# INF_Pro_Interface.net
KiCad netlist of a schematic drawn in Altium Designer
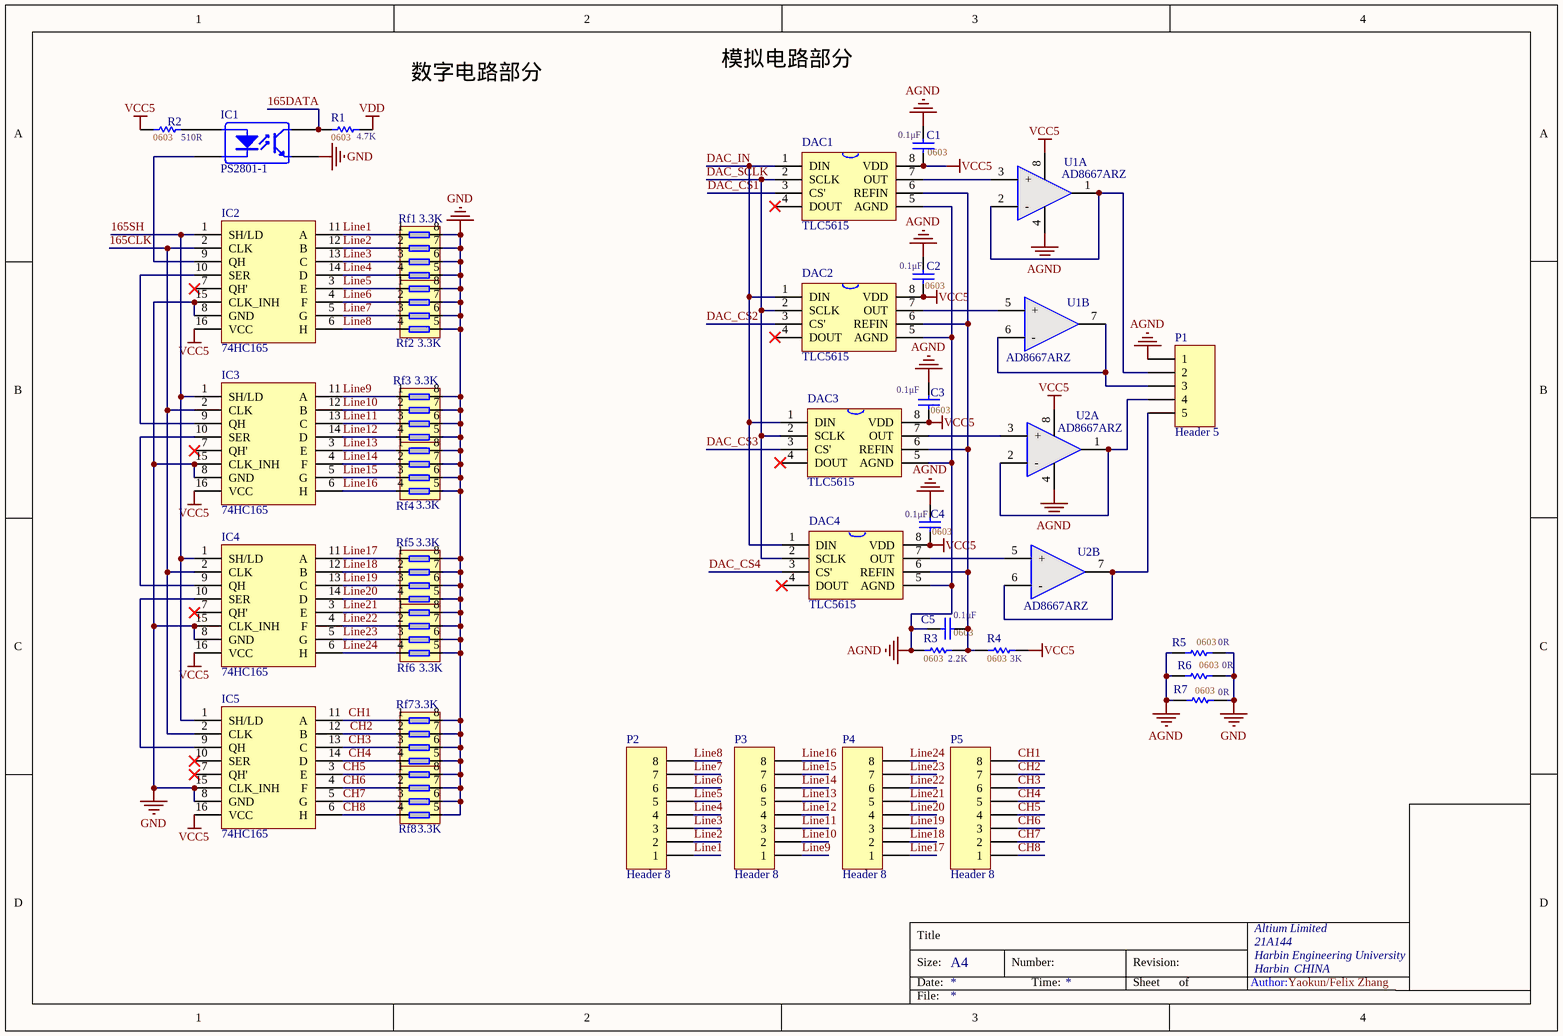
[diagram p0: INF_Pro_Interface.SchDoc]

(export (version "E")
  (design (tool "Eeschema 10.0.6"))
  (components
    (comp (ref "C1")
      (value "0.1μF")
      (footprint "CAP_0603_16*08")
      (description "Capacitor")
      (fields
        (field (name "PACKAGEREFERENCE") "0603")
        (field (name "Comment") "0603")
        (field (name "PUBLISHER") "Altium Limited")
      )
      (libsource (lib "Belong_to_Kongkong") (part "Cap"))
    )
    (comp (ref "C2")
      (value "0.1μF")
      (footprint "CAP_0603_16*08")
      (description "Capacitor")
      (fields
        (field (name "PACKAGEREFERENCE") "0603")
        (field (name "Comment") "0603")
        (field (name "PUBLISHER") "Altium Limited")
      )
      (libsource (lib "Belong_to_Kongkong") (part "Cap"))
    )
    (comp (ref "C3")
      (value "0.1μF")
      (footprint "CAP_0603_16*08")
      (description "Capacitor")
      (fields
        (field (name "PACKAGEREFERENCE") "0603")
        (field (name "Comment") "0603")
        (field (name "PUBLISHER") "Altium Limited")
      )
      (libsource (lib "Belong_to_Kongkong") (part "Cap"))
    )
    (comp (ref "C4")
      (value "0.1μF")
      (footprint "CAP_0603_16*08")
      (description "Capacitor")
      (fields
        (field (name "PACKAGEREFERENCE") "0603")
        (field (name "Comment") "0603")
        (field (name "PUBLISHER") "Altium Limited")
      )
      (libsource (lib "Belong_to_Kongkong") (part "Cap"))
    )
    (comp (ref "C5")
      (value "0.1μF")
      (footprint "CAP_0603_16*08")
      (description "Capacitor")
      (fields
        (field (name "PACKAGEREFERENCE") "0603")
        (field (name "Comment") "0603")
        (field (name "PUBLISHER") "Altium Limited")
      )
      (libsource (lib "Belong_to_Kongkong") (part "Cap"))
    )
    (comp (ref "DAC1")
      (value "TLC5615")
      (footprint "DIP-8")
      (libsource (lib "Belong_to_Kongkong") (part "TLC5616_DAC"))
    )
    (comp (ref "DAC2")
      (value "TLC5615")
      (footprint "DIP-8")
      (libsource (lib "Belong_to_Kongkong") (part "TLC5616_DAC"))
    )
    (comp (ref "DAC3")
      (value "TLC5615")
      (footprint "DIP-8")
      (libsource (lib "Belong_to_Kongkong") (part "TLC5616_DAC"))
    )
    (comp (ref "DAC4")
      (value "TLC5615")
      (footprint "DIP-8")
      (libsource (lib "Belong_to_Kongkong") (part "TLC5616_DAC"))
    )
    (comp (ref "IC1")
      (value "PS2801-1")
      (footprint "DIP-4")
      (libsource (lib "Belong_to_Kongkong") (part "PS2801-1"))
    )
    (comp (ref "IC2")
      (value "74HC165")
      (footprint "DIP-16")
      (libsource (lib "Belong_to_Kongkong") (part "74HC165"))
    )
    (comp (ref "IC3")
      (value "74HC165")
      (footprint "DIP-16")
      (libsource (lib "Belong_to_Kongkong") (part "74HC165"))
    )
    (comp (ref "IC4")
      (value "74HC165")
      (footprint "DIP-16")
      (libsource (lib "Belong_to_Kongkong") (part "74HC165"))
    )
    (comp (ref "IC5")
      (value "74HC165")
      (footprint "DIP-16")
      (libsource (lib "Belong_to_Kongkong") (part "74HC165"))
    )
    (comp (ref "P1")
      (value "Header 5")
      (footprint "P5_OUT")
      (description "Header, 5-Pin")
      (fields (field (name "PUBLISHER") "Altium Limited"))
      (libsource (lib "Belong_to_Kongkong") (part "Header 5"))
    )
    (comp (ref "P2")
      (value "Header 8")
      (footprint "P8_OUT")
      (description "Header, 8-Pin")
      (fields (field (name "PUBLISHER") "Altium Limited"))
      (libsource (lib "Belong_to_Kongkong") (part "Header 8"))
    )
    (comp (ref "P3")
      (value "Header 8")
      (footprint "P8_OUT")
      (description "Header, 8-Pin")
      (fields (field (name "PUBLISHER") "Altium Limited"))
      (libsource (lib "Belong_to_Kongkong") (part "Header 8"))
    )
    (comp (ref "P4")
      (value "Header 8")
      (footprint "P8_OUT")
      (description "Header, 8-Pin")
      (fields (field (name "PUBLISHER") "Altium Limited"))
      (libsource (lib "Belong_to_Kongkong") (part "Header 8"))
    )
    (comp (ref "P5")
      (value "Header 8")
      (footprint "P8_OUT")
      (description "Header, 8-Pin")
      (fields (field (name "PUBLISHER") "Altium Limited"))
      (libsource (lib "Belong_to_Kongkong") (part "Header 8"))
    )
    (comp (ref "R1")
      (value "4.7K")
      (footprint "RES_0805_20*12")
      (description "Resistor")
      (fields
        (field (name "PACKAGEREFERENCE") "0603")
        (field (name "Comment") "SMD")
        (field (name "PUBLISHER") "Altium Limited")
      )
      (libsource (lib "Belong_to_Kongkong") (part "RES_SMD"))
    )
    (comp (ref "R2")
      (value "510R")
      (footprint "RES_0805_20*12")
      (description "Resistor")
      (fields
        (field (name "PACKAGEREFERENCE") "0603")
        (field (name "Comment") "SMD")
        (field (name "PUBLISHER") "Altium Limited")
      )
      (libsource (lib "Belong_to_Kongkong") (part "RES_SMD"))
    )
    (comp (ref "R3")
      (value "2.2K")
      (footprint "RES_0805_20*12")
      (description "Resistor")
      (fields
        (field (name "PACKAGEREFERENCE") "0603")
        (field (name "Comment") "SMD")
        (field (name "PUBLISHER") "Altium Limited")
      )
      (libsource (lib "Belong_to_Kongkong") (part "RES_SMD"))
    )
    (comp (ref "R4")
      (value "3K")
      (footprint "RES_0805_20*12")
      (description "Resistor")
      (fields
        (field (name "PACKAGEREFERENCE") "0603")
        (field (name "Comment") "SMD")
        (field (name "PUBLISHER") "Altium Limited")
      )
      (libsource (lib "Belong_to_Kongkong") (part "RES_SMD"))
    )
    (comp (ref "R5")
      (value "0R")
      (footprint "RES_0805_20*12")
      (description "Resistor")
      (fields
        (field (name "PACKAGEREFERENCE") "0603")
        (field (name "Comment") "SMD")
        (field (name "PUBLISHER") "Altium Limited")
      )
      (libsource (lib "Belong_to_Kongkong") (part "RES_SMD"))
    )
    (comp (ref "R6")
      (value "0R")
      (footprint "RES_0805_20*12")
      (description "Resistor")
      (fields
        (field (name "PACKAGEREFERENCE") "0603")
        (field (name "Comment") "SMD")
        (field (name "PUBLISHER") "Altium Limited")
      )
      (libsource (lib "Belong_to_Kongkong") (part "RES_SMD"))
    )
    (comp (ref "R7")
      (value "0R")
      (footprint "RES_0805_20*12")
      (description "Resistor")
      (fields
        (field (name "PACKAGEREFERENCE") "0603")
        (field (name "Comment") "SMD")
        (field (name "PUBLISHER") "Altium Limited")
      )
      (libsource (lib "Belong_to_Kongkong") (part "RES_SMD"))
    )
    (comp (ref "Rf1")
      (value "3.3K")
      (footprint "RES_FOUR_0603")
      (libsource (lib "Belong_to_Kongkong") (part "RES_4P"))
    )
    (comp (ref "Rf2")
      (value "3.3K")
      (footprint "RES_FOUR_0603")
      (libsource (lib "Belong_to_Kongkong") (part "RES_4P"))
    )
    (comp (ref "Rf3")
      (value "3.3K")
      (footprint "RES_FOUR_0603")
      (libsource (lib "Belong_to_Kongkong") (part "RES_4P"))
    )
    (comp (ref "Rf4")
      (value "3.3K")
      (footprint "RES_FOUR_0603")
      (libsource (lib "Belong_to_Kongkong") (part "RES_4P"))
    )
    (comp (ref "Rf5")
      (value "3.3K")
      (footprint "RES_FOUR_0603")
      (libsource (lib "Belong_to_Kongkong") (part "RES_4P"))
    )
    (comp (ref "Rf6")
      (value "3.3K")
      (footprint "RES_FOUR_0603")
      (libsource (lib "Belong_to_Kongkong") (part "RES_4P"))
    )
    (comp (ref "Rf7")
      (value "3.3K")
      (footprint "RES_FOUR_0603")
      (libsource (lib "Belong_to_Kongkong") (part "RES_4P"))
    )
    (comp (ref "Rf8")
      (value "3.3K")
      (footprint "RES_FOUR_0603")
      (libsource (lib "Belong_to_Kongkong") (part "RES_4P"))
    )
    (comp (ref "U1")
      (value "AD8667ARZ")
      (footprint "DIP-8")
      (description "双运放")
      (libsource (lib "Belong_to_Kongkong") (part "AD8667"))
    )
    (comp (ref "U2")
      (value "AD8667ARZ")
      (footprint "DIP-8")
      (description "双运放")
      (libsource (lib "Belong_to_Kongkong") (part "AD8667"))
    )
  )
  (nets
    (net (code "1") (name "/165CLK") (class "Default")
      (node (ref "IC2") (pin "2") (pinfunction "CLK_2") (pintype "passive"))
      (node (ref "IC3") (pin "2") (pinfunction "CLK_2") (pintype "passive"))
      (node (ref "IC4") (pin "2") (pinfunction "CLK_2") (pintype "passive"))
      (node (ref "IC5") (pin "2") (pinfunction "CLK_2") (pintype "passive"))
    )
    (net (code "2") (name "/165DATA") (class "Default")
      (node (ref "IC1") (pin "4") (pinfunction "4_4") (pintype "passive"))
      (node (ref "R1") (pin "1") (pinfunction "1_1") (pintype "passive"))
    )
    (net (code "3") (name "/165SH") (class "Default")
      (node (ref "IC2") (pin "1") (pinfunction "SH/LD_1") (pintype "passive"))
      (node (ref "IC3") (pin "1") (pinfunction "SH/LD_1") (pintype "passive"))
      (node (ref "IC4") (pin "1") (pinfunction "SH/LD_1") (pintype "passive"))
      (node (ref "IC5") (pin "1") (pinfunction "SH/LD_1") (pintype "passive"))
    )
    (net (code "4") (name "/CH1") (class "Default")
      (node (ref "IC5") (pin "11") (pinfunction "A_11") (pintype "passive"))
      (node (ref "P5") (pin "8") (pinfunction "8_8") (pintype "passive"))
      (node (ref "Rf7") (pin "1") (pinfunction "1_1") (pintype "passive"))
    )
    (net (code "5") (name "/CH2") (class "Default")
      (node (ref "IC5") (pin "12") (pinfunction "B_12") (pintype "passive"))
      (node (ref "P5") (pin "7") (pinfunction "7_7") (pintype "passive"))
      (node (ref "Rf7") (pin "2") (pinfunction "2_2") (pintype "passive"))
    )
    (net (code "6") (name "/CH3") (class "Default")
      (node (ref "IC5") (pin "13") (pinfunction "C_13") (pintype "passive"))
      (node (ref "P5") (pin "6") (pinfunction "6_6") (pintype "passive"))
      (node (ref "Rf7") (pin "3") (pinfunction "3_3") (pintype "passive"))
    )
    (net (code "7") (name "/CH4") (class "Default")
      (node (ref "IC5") (pin "14") (pinfunction "D_14") (pintype "passive"))
      (node (ref "P5") (pin "5") (pinfunction "5_5") (pintype "passive"))
      (node (ref "Rf7") (pin "4") (pinfunction "4_4") (pintype "passive"))
    )
    (net (code "8") (name "/CH5") (class "Default")
      (node (ref "IC5") (pin "3") (pinfunction "E_3") (pintype "passive"))
      (node (ref "P5") (pin "4") (pinfunction "4_4") (pintype "passive"))
      (node (ref "Rf8") (pin "1") (pinfunction "1_1") (pintype "passive"))
    )
    (net (code "9") (name "/CH6") (class "Default")
      (node (ref "IC5") (pin "4") (pinfunction "F_4") (pintype "passive"))
      (node (ref "P5") (pin "3") (pinfunction "3_3") (pintype "passive"))
      (node (ref "Rf8") (pin "2") (pinfunction "2_2") (pintype "passive"))
    )
    (net (code "10") (name "/CH7") (class "Default")
      (node (ref "IC5") (pin "5") (pinfunction "G_5") (pintype "passive"))
      (node (ref "P5") (pin "2") (pinfunction "2_2") (pintype "passive"))
      (node (ref "Rf8") (pin "3") (pinfunction "3_3") (pintype "passive"))
    )
    (net (code "11") (name "/CH8") (class "Default")
      (node (ref "IC5") (pin "6") (pinfunction "H_6") (pintype "passive"))
      (node (ref "P5") (pin "1") (pinfunction "1_1") (pintype "passive"))
      (node (ref "Rf8") (pin "4") (pinfunction "4_4") (pintype "passive"))
    )
    (net (code "12") (name "/DAC_CS1") (class "Default")
      (node (ref "DAC1") (pin "3") (pinfunction "CS'_3") (pintype "passive"))
    )
    (net (code "13") (name "/DAC_CS2") (class "Default")
      (node (ref "DAC2") (pin "3") (pinfunction "CS'_3") (pintype "passive"))
    )
    (net (code "14") (name "/DAC_CS3") (class "Default")
      (node (ref "DAC3") (pin "3") (pinfunction "CS'_3") (pintype "passive"))
    )
    (net (code "15") (name "/DAC_CS4") (class "Default")
      (node (ref "DAC4") (pin "3") (pinfunction "CS'_3") (pintype "passive"))
    )
    (net (code "16") (name "/DAC_IN") (class "Default")
      (node (ref "DAC1") (pin "1") (pinfunction "DIN_1") (pintype "passive"))
      (node (ref "DAC2") (pin "1") (pinfunction "DIN_1") (pintype "passive"))
      (node (ref "DAC3") (pin "1") (pinfunction "DIN_1") (pintype "passive"))
      (node (ref "DAC4") (pin "1") (pinfunction "DIN_1") (pintype "passive"))
    )
    (net (code "17") (name "/DAC_SCLK") (class "Default")
      (node (ref "DAC1") (pin "2") (pinfunction "SCLK_2") (pintype "passive"))
      (node (ref "DAC2") (pin "2") (pinfunction "SCLK_2") (pintype "passive"))
      (node (ref "DAC3") (pin "2") (pinfunction "SCLK_2") (pintype "passive"))
      (node (ref "DAC4") (pin "2") (pinfunction "SCLK_2") (pintype "passive"))
    )
    (net (code "18") (name "/Line1") (class "Default")
      (node (ref "IC2") (pin "11") (pinfunction "A_11") (pintype "passive"))
      (node (ref "P2") (pin "1") (pinfunction "1_1") (pintype "passive"))
      (node (ref "Rf1") (pin "1") (pinfunction "1_1") (pintype "passive"))
    )
    (net (code "19") (name "/Line2") (class "Default")
      (node (ref "IC2") (pin "12") (pinfunction "B_12") (pintype "passive"))
      (node (ref "P2") (pin "2") (pinfunction "2_2") (pintype "passive"))
      (node (ref "Rf1") (pin "2") (pinfunction "2_2") (pintype "passive"))
    )
    (net (code "20") (name "/Line3") (class "Default")
      (node (ref "IC2") (pin "13") (pinfunction "C_13") (pintype "passive"))
      (node (ref "P2") (pin "3") (pinfunction "3_3") (pintype "passive"))
      (node (ref "Rf1") (pin "3") (pinfunction "3_3") (pintype "passive"))
    )
    (net (code "21") (name "/Line4") (class "Default")
      (node (ref "IC2") (pin "14") (pinfunction "D_14") (pintype "passive"))
      (node (ref "P2") (pin "4") (pinfunction "4_4") (pintype "passive"))
      (node (ref "Rf1") (pin "4") (pinfunction "4_4") (pintype "passive"))
    )
    (net (code "22") (name "/Line5") (class "Default")
      (node (ref "IC2") (pin "3") (pinfunction "E_3") (pintype "passive"))
      (node (ref "P2") (pin "5") (pinfunction "5_5") (pintype "passive"))
      (node (ref "Rf2") (pin "1") (pinfunction "1_1") (pintype "passive"))
    )
    (net (code "23") (name "/Line6") (class "Default")
      (node (ref "IC2") (pin "4") (pinfunction "F_4") (pintype "passive"))
      (node (ref "P2") (pin "6") (pinfunction "6_6") (pintype "passive"))
      (node (ref "Rf2") (pin "2") (pinfunction "2_2") (pintype "passive"))
    )
    (net (code "24") (name "/Line7") (class "Default")
      (node (ref "IC2") (pin "5") (pinfunction "G_5") (pintype "passive"))
      (node (ref "P2") (pin "7") (pinfunction "7_7") (pintype "passive"))
      (node (ref "Rf2") (pin "3") (pinfunction "3_3") (pintype "passive"))
    )
    (net (code "25") (name "/Line8") (class "Default")
      (node (ref "IC2") (pin "6") (pinfunction "H_6") (pintype "passive"))
      (node (ref "P2") (pin "8") (pinfunction "8_8") (pintype "passive"))
      (node (ref "Rf2") (pin "4") (pinfunction "4_4") (pintype "passive"))
    )
    (net (code "26") (name "/Line9") (class "Default")
      (node (ref "IC3") (pin "11") (pinfunction "A_11") (pintype "passive"))
      (node (ref "P3") (pin "1") (pinfunction "1_1") (pintype "passive"))
      (node (ref "Rf3") (pin "1") (pinfunction "1_1") (pintype "passive"))
    )
    (net (code "27") (name "/Line10") (class "Default")
      (node (ref "IC3") (pin "12") (pinfunction "B_12") (pintype "passive"))
      (node (ref "P3") (pin "2") (pinfunction "2_2") (pintype "passive"))
      (node (ref "Rf3") (pin "2") (pinfunction "2_2") (pintype "passive"))
    )
    (net (code "28") (name "/Line11") (class "Default")
      (node (ref "IC3") (pin "13") (pinfunction "C_13") (pintype "passive"))
      (node (ref "P3") (pin "3") (pinfunction "3_3") (pintype "passive"))
      (node (ref "Rf3") (pin "3") (pinfunction "3_3") (pintype "passive"))
    )
    (net (code "29") (name "/Line12") (class "Default")
      (node (ref "IC3") (pin "14") (pinfunction "D_14") (pintype "passive"))
      (node (ref "P3") (pin "4") (pinfunction "4_4") (pintype "passive"))
      (node (ref "Rf3") (pin "4") (pinfunction "4_4") (pintype "passive"))
    )
    (net (code "30") (name "/Line13") (class "Default")
      (node (ref "IC3") (pin "3") (pinfunction "E_3") (pintype "passive"))
      (node (ref "P3") (pin "5") (pinfunction "5_5") (pintype "passive"))
      (node (ref "Rf4") (pin "1") (pinfunction "1_1") (pintype "passive"))
    )
    (net (code "31") (name "/Line14") (class "Default")
      (node (ref "IC3") (pin "4") (pinfunction "F_4") (pintype "passive"))
      (node (ref "P3") (pin "6") (pinfunction "6_6") (pintype "passive"))
      (node (ref "Rf4") (pin "2") (pinfunction "2_2") (pintype "passive"))
    )
    (net (code "32") (name "/Line15") (class "Default")
      (node (ref "IC3") (pin "5") (pinfunction "G_5") (pintype "passive"))
      (node (ref "P3") (pin "7") (pinfunction "7_7") (pintype "passive"))
      (node (ref "Rf4") (pin "3") (pinfunction "3_3") (pintype "passive"))
    )
    (net (code "33") (name "/Line16") (class "Default")
      (node (ref "IC3") (pin "6") (pinfunction "H_6") (pintype "passive"))
      (node (ref "P3") (pin "8") (pinfunction "8_8") (pintype "passive"))
      (node (ref "Rf4") (pin "4") (pinfunction "4_4") (pintype "passive"))
    )
    (net (code "34") (name "/Line17") (class "Default")
      (node (ref "IC4") (pin "11") (pinfunction "A_11") (pintype "passive"))
      (node (ref "P4") (pin "1") (pinfunction "1_1") (pintype "passive"))
      (node (ref "Rf5") (pin "1") (pinfunction "1_1") (pintype "passive"))
    )
    (net (code "35") (name "/Line18") (class "Default")
      (node (ref "IC4") (pin "12") (pinfunction "B_12") (pintype "passive"))
      (node (ref "P4") (pin "2") (pinfunction "2_2") (pintype "passive"))
      (node (ref "Rf5") (pin "2") (pinfunction "2_2") (pintype "passive"))
    )
    (net (code "36") (name "/Line19") (class "Default")
      (node (ref "IC4") (pin "13") (pinfunction "C_13") (pintype "passive"))
      (node (ref "P4") (pin "3") (pinfunction "3_3") (pintype "passive"))
      (node (ref "Rf5") (pin "3") (pinfunction "3_3") (pintype "passive"))
    )
    (net (code "37") (name "/Line20") (class "Default")
      (node (ref "IC4") (pin "14") (pinfunction "D_14") (pintype "passive"))
      (node (ref "P4") (pin "4") (pinfunction "4_4") (pintype "passive"))
      (node (ref "Rf5") (pin "4") (pinfunction "4_4") (pintype "passive"))
    )
    (net (code "38") (name "/Line21") (class "Default")
      (node (ref "IC4") (pin "3") (pinfunction "E_3") (pintype "passive"))
      (node (ref "P4") (pin "5") (pinfunction "5_5") (pintype "passive"))
      (node (ref "Rf6") (pin "1") (pinfunction "1_1") (pintype "passive"))
    )
    (net (code "39") (name "/Line22") (class "Default")
      (node (ref "IC4") (pin "4") (pinfunction "F_4") (pintype "passive"))
      (node (ref "P4") (pin "6") (pinfunction "6_6") (pintype "passive"))
      (node (ref "Rf6") (pin "2") (pinfunction "2_2") (pintype "passive"))
    )
    (net (code "40") (name "/Line23") (class "Default")
      (node (ref "IC4") (pin "5") (pinfunction "G_5") (pintype "passive"))
      (node (ref "P4") (pin "7") (pinfunction "7_7") (pintype "passive"))
      (node (ref "Rf6") (pin "3") (pinfunction "3_3") (pintype "passive"))
    )
    (net (code "41") (name "/Line24") (class "Default")
      (node (ref "IC4") (pin "6") (pinfunction "H_6") (pintype "passive"))
      (node (ref "P4") (pin "8") (pinfunction "8_8") (pintype "passive"))
      (node (ref "Rf6") (pin "4") (pinfunction "4_4") (pintype "passive"))
    )
    (net (code "42") (name "AGND") (class "Default")
      (node (ref "C1") (pin "2") (pinfunction "2_2") (pintype "passive"))
      (node (ref "C2") (pin "2") (pinfunction "2_2") (pintype "passive"))
      (node (ref "C3") (pin "2") (pinfunction "2_2") (pintype "passive"))
      (node (ref "C4") (pin "2") (pinfunction "2_2") (pintype "passive"))
      (node (ref "C5") (pin "1") (pinfunction "1_1") (pintype "passive"))
      (node (ref "DAC1") (pin "5") (pinfunction "AGND_5") (pintype "passive"))
      (node (ref "DAC2") (pin "5") (pinfunction "AGND_5") (pintype "passive"))
      (node (ref "DAC3") (pin "5") (pinfunction "AGND_5") (pintype "passive"))
      (node (ref "DAC4") (pin "5") (pinfunction "AGND_5") (pintype "passive"))
      (node (ref "P1") (pin "1") (pinfunction "1_1") (pintype "passive"))
      (node (ref "R3") (pin "2") (pinfunction "2_2") (pintype "passive"))
      (node (ref "R5") (pin "1") (pinfunction "1_1") (pintype "passive"))
      (node (ref "R6") (pin "1") (pinfunction "1_1") (pintype "passive"))
      (node (ref "R7") (pin "1") (pinfunction "1_1") (pintype "passive"))
      (node (ref "U1") (pin "4") (pinfunction "V-_4") (pintype "power_in"))
      (node (ref "U2") (pin "4") (pinfunction "V-_4") (pintype "power_in"))
    )
    (net (code "43") (name "GND") (class "Default")
      (node (ref "IC1") (pin "3") (pinfunction "3_3") (pintype "passive"))
      (node (ref "IC2") (pin "15") (pinfunction "CLK_INH_15") (pintype "passive"))
      (node (ref "IC2") (pin "8") (pinfunction "GND_8") (pintype "passive"))
      (node (ref "IC3") (pin "15") (pinfunction "CLK_INH_15") (pintype "passive"))
      (node (ref "IC3") (pin "8") (pinfunction "GND_8") (pintype "passive"))
      (node (ref "IC4") (pin "15") (pinfunction "CLK_INH_15") (pintype "passive"))
      (node (ref "IC4") (pin "8") (pinfunction "GND_8") (pintype "passive"))
      (node (ref "IC5") (pin "15") (pinfunction "CLK_INH_15") (pintype "passive"))
      (node (ref "IC5") (pin "8") (pinfunction "GND_8") (pintype "passive"))
      (node (ref "R5") (pin "2") (pinfunction "2_2") (pintype "passive"))
      (node (ref "R6") (pin "2") (pinfunction "2_2") (pintype "passive"))
      (node (ref "R7") (pin "2") (pinfunction "2_2") (pintype "passive"))
      (node (ref "Rf1") (pin "5") (pinfunction "5_5") (pintype "passive"))
      (node (ref "Rf1") (pin "6") (pinfunction "6_6") (pintype "passive"))
      (node (ref "Rf1") (pin "7") (pinfunction "7_7") (pintype "passive"))
      (node (ref "Rf1") (pin "8") (pinfunction "8_8") (pintype "passive"))
      (node (ref "Rf2") (pin "5") (pinfunction "5_5") (pintype "passive"))
      (node (ref "Rf2") (pin "6") (pinfunction "6_6") (pintype "passive"))
      (node (ref "Rf2") (pin "7") (pinfunction "7_7") (pintype "passive"))
      (node (ref "Rf2") (pin "8") (pinfunction "8_8") (pintype "passive"))
      (node (ref "Rf3") (pin "5") (pinfunction "5_5") (pintype "passive"))
      (node (ref "Rf3") (pin "6") (pinfunction "6_6") (pintype "passive"))
      (node (ref "Rf3") (pin "7") (pinfunction "7_7") (pintype "passive"))
      (node (ref "Rf3") (pin "8") (pinfunction "8_8") (pintype "passive"))
      (node (ref "Rf4") (pin "5") (pinfunction "5_5") (pintype "passive"))
      (node (ref "Rf4") (pin "6") (pinfunction "6_6") (pintype "passive"))
      (node (ref "Rf4") (pin "7") (pinfunction "7_7") (pintype "passive"))
      (node (ref "Rf4") (pin "8") (pinfunction "8_8") (pintype "passive"))
      (node (ref "Rf5") (pin "5") (pinfunction "5_5") (pintype "passive"))
      (node (ref "Rf5") (pin "6") (pinfunction "6_6") (pintype "passive"))
      (node (ref "Rf5") (pin "7") (pinfunction "7_7") (pintype "passive"))
      (node (ref "Rf5") (pin "8") (pinfunction "8_8") (pintype "passive"))
      (node (ref "Rf6") (pin "5") (pinfunction "5_5") (pintype "passive"))
      (node (ref "Rf6") (pin "6") (pinfunction "6_6") (pintype "passive"))
      (node (ref "Rf6") (pin "7") (pinfunction "7_7") (pintype "passive"))
      (node (ref "Rf6") (pin "8") (pinfunction "8_8") (pintype "passive"))
      (node (ref "Rf7") (pin "5") (pinfunction "5_5") (pintype "passive"))
      (node (ref "Rf7") (pin "6") (pinfunction "6_6") (pintype "passive"))
      (node (ref "Rf7") (pin "7") (pinfunction "7_7") (pintype "passive"))
      (node (ref "Rf7") (pin "8") (pinfunction "8_8") (pintype "passive"))
      (node (ref "Rf8") (pin "5") (pinfunction "5_5") (pintype "passive"))
      (node (ref "Rf8") (pin "6") (pinfunction "6_6") (pintype "passive"))
      (node (ref "Rf8") (pin "7") (pinfunction "7_7") (pintype "passive"))
      (node (ref "Rf8") (pin "8") (pinfunction "8_8") (pintype "passive"))
    )
    (net (code "44") (name "Net-(DAC1-OUT)") (class "Default")
      (node (ref "DAC1") (pin "7") (pinfunction "OUT_7") (pintype "passive"))
      (node (ref "U1") (pin "3") (pinfunction "+_3") (pintype "passive"))
    )
    (net (code "45") (name "Net-(DAC1-REFIN)") (class "Default")
      (node (ref "C5") (pin "2") (pinfunction "2_2") (pintype "passive"))
      (node (ref "DAC1") (pin "6") (pinfunction "REFIN_6") (pintype "passive"))
      (node (ref "DAC2") (pin "6") (pinfunction "REFIN_6") (pintype "passive"))
      (node (ref "DAC3") (pin "6") (pinfunction "REFIN_6") (pintype "passive"))
      (node (ref "DAC4") (pin "6") (pinfunction "REFIN_6") (pintype "passive"))
      (node (ref "R3") (pin "1") (pinfunction "1_1") (pintype "passive"))
      (node (ref "R4") (pin "2") (pinfunction "2_2") (pintype "passive"))
    )
    (net (code "46") (name "Net-(DAC2-OUT)") (class "Default")
      (node (ref "DAC2") (pin "7") (pinfunction "OUT_7") (pintype "passive"))
      (node (ref "U1") (pin "5") (pinfunction "+_5") (pintype "passive"))
    )
    (net (code "47") (name "Net-(DAC3-OUT)") (class "Default")
      (node (ref "DAC3") (pin "7") (pinfunction "OUT_7") (pintype "passive"))
      (node (ref "U2") (pin "3") (pinfunction "+_3") (pintype "passive"))
    )
    (net (code "48") (name "Net-(DAC4-OUT)") (class "Default")
      (node (ref "DAC4") (pin "7") (pinfunction "OUT_7") (pintype "passive"))
      (node (ref "U2") (pin "5") (pinfunction "+_5") (pintype "passive"))
    )
    (net (code "49") (name "Net-(IC1-Pad1)") (class "Default")
      (node (ref "IC1") (pin "1") (pinfunction "1_1") (pintype "passive"))
      (node (ref "R2") (pin "2") (pinfunction "2_2") (pintype "passive"))
    )
    (net (code "50") (name "Net-(IC2-QH)") (class "Default")
      (node (ref "IC1") (pin "2") (pinfunction "2_2") (pintype "passive"))
      (node (ref "IC2") (pin "9") (pinfunction "QH_9") (pintype "passive"))
    )
    (net (code "51") (name "Net-(IC2-SER)") (class "Default")
      (node (ref "IC2") (pin "10") (pinfunction "SER_10") (pintype "passive"))
      (node (ref "IC3") (pin "9") (pinfunction "QH_9") (pintype "passive"))
    )
    (net (code "52") (name "Net-(IC3-SER)") (class "Default")
      (node (ref "IC3") (pin "10") (pinfunction "SER_10") (pintype "passive"))
      (node (ref "IC4") (pin "9") (pinfunction "QH_9") (pintype "passive"))
    )
    (net (code "53") (name "Net-(IC4-SER)") (class "Default")
      (node (ref "IC4") (pin "10") (pinfunction "SER_10") (pintype "passive"))
      (node (ref "IC5") (pin "9") (pinfunction "QH_9") (pintype "passive"))
    )
    (net (code "54") (name "Net-(U1A--)") (class "Default")
      (node (ref "P1") (pin "2") (pinfunction "2_2") (pintype "passive"))
      (node (ref "U1") (pin "1") (pinfunction "OUT1_1") (pintype "passive"))
      (node (ref "U1") (pin "2") (pinfunction "-_2") (pintype "passive"))
    )
    (net (code "55") (name "Net-(U1B--)") (class "Default")
      (node (ref "P1") (pin "3") (pinfunction "3_3") (pintype "passive"))
      (node (ref "U1") (pin "6") (pinfunction "-_6") (pintype "passive"))
      (node (ref "U1") (pin "7") (pinfunction "OUT2_7") (pintype "passive"))
    )
    (net (code "56") (name "Net-(U2A--)") (class "Default")
      (node (ref "P1") (pin "4") (pinfunction "4_4") (pintype "passive"))
      (node (ref "U2") (pin "1") (pinfunction "OUT1_1") (pintype "passive"))
      (node (ref "U2") (pin "2") (pinfunction "-_2") (pintype "passive"))
    )
    (net (code "57") (name "Net-(U2B--)") (class "Default")
      (node (ref "P1") (pin "5") (pinfunction "5_5") (pintype "passive"))
      (node (ref "U2") (pin "6") (pinfunction "-_6") (pintype "passive"))
      (node (ref "U2") (pin "7") (pinfunction "OUT2_7") (pintype "passive"))
    )
    (net (code "58") (name "VCC5") (class "Default")
      (node (ref "C1") (pin "1") (pinfunction "1_1") (pintype "passive"))
      (node (ref "C2") (pin "1") (pinfunction "1_1") (pintype "passive"))
      (node (ref "C3") (pin "1") (pinfunction "1_1") (pintype "passive"))
      (node (ref "C4") (pin "1") (pinfunction "1_1") (pintype "passive"))
      (node (ref "DAC1") (pin "8") (pinfunction "VDD_8") (pintype "passive"))
      (node (ref "DAC2") (pin "8") (pinfunction "VDD_8") (pintype "passive"))
      (node (ref "DAC3") (pin "8") (pinfunction "VDD_8") (pintype "passive"))
      (node (ref "DAC4") (pin "8") (pinfunction "VDD_8") (pintype "passive"))
      (node (ref "IC2") (pin "16") (pinfunction "VCC_16") (pintype "passive"))
      (node (ref "IC3") (pin "16") (pinfunction "VCC_16") (pintype "passive"))
      (node (ref "IC4") (pin "16") (pinfunction "VCC_16") (pintype "passive"))
      (node (ref "IC5") (pin "16") (pinfunction "VCC_16") (pintype "passive"))
      (node (ref "R2") (pin "1") (pinfunction "1_1") (pintype "passive"))
      (node (ref "R4") (pin "1") (pinfunction "1_1") (pintype "passive"))
      (node (ref "U1") (pin "8") (pinfunction "V+_8") (pintype "power_in"))
      (node (ref "U2") (pin "8") (pinfunction "V+_8") (pintype "power_in"))
    )
    (net (code "59") (name "VDD") (class "Default")
      (node (ref "R1") (pin "2") (pinfunction "2_2") (pintype "passive"))
    )
    (net (code "60") (name "unconnected-(DAC1-DOUT-Pad4)") (class "Default")
      (node (ref "DAC1") (pin "4") (pinfunction "DOUT_4") (pintype "passive+no_connect"))
    )
    (net (code "61") (name "unconnected-(DAC2-DOUT-Pad4)") (class "Default")
      (node (ref "DAC2") (pin "4") (pinfunction "DOUT_4") (pintype "passive+no_connect"))
    )
    (net (code "62") (name "unconnected-(DAC3-DOUT-Pad4)") (class "Default")
      (node (ref "DAC3") (pin "4") (pinfunction "DOUT_4") (pintype "passive+no_connect"))
    )
    (net (code "63") (name "unconnected-(DAC4-DOUT-Pad4)") (class "Default")
      (node (ref "DAC4") (pin "4") (pinfunction "DOUT_4") (pintype "passive+no_connect"))
    )
    (net (code "64") (name "unconnected-(IC2-QH'-Pad7)") (class "Default")
      (node (ref "IC2") (pin "7") (pinfunction "QH'_7") (pintype "passive+no_connect"))
    )
    (net (code "65") (name "unconnected-(IC3-QH'-Pad7)") (class "Default")
      (node (ref "IC3") (pin "7") (pinfunction "QH'_7") (pintype "passive+no_connect"))
    )
    (net (code "66") (name "unconnected-(IC4-QH'-Pad7)") (class "Default")
      (node (ref "IC4") (pin "7") (pinfunction "QH'_7") (pintype "passive+no_connect"))
    )
    (net (code "67") (name "unconnected-(IC5-QH'-Pad7)") (class "Default")
      (node (ref "IC5") (pin "7") (pinfunction "QH'_7") (pintype "passive+no_connect"))
    )
    (net (code "68") (name "unconnected-(IC5-SER-Pad10)") (class "Default")
      (node (ref "IC5") (pin "10") (pinfunction "SER_10") (pintype "passive+no_connect"))
    )
  )
)
